# thermo_r1.net
KiCad netlist of a schematic drawn in EAGLE
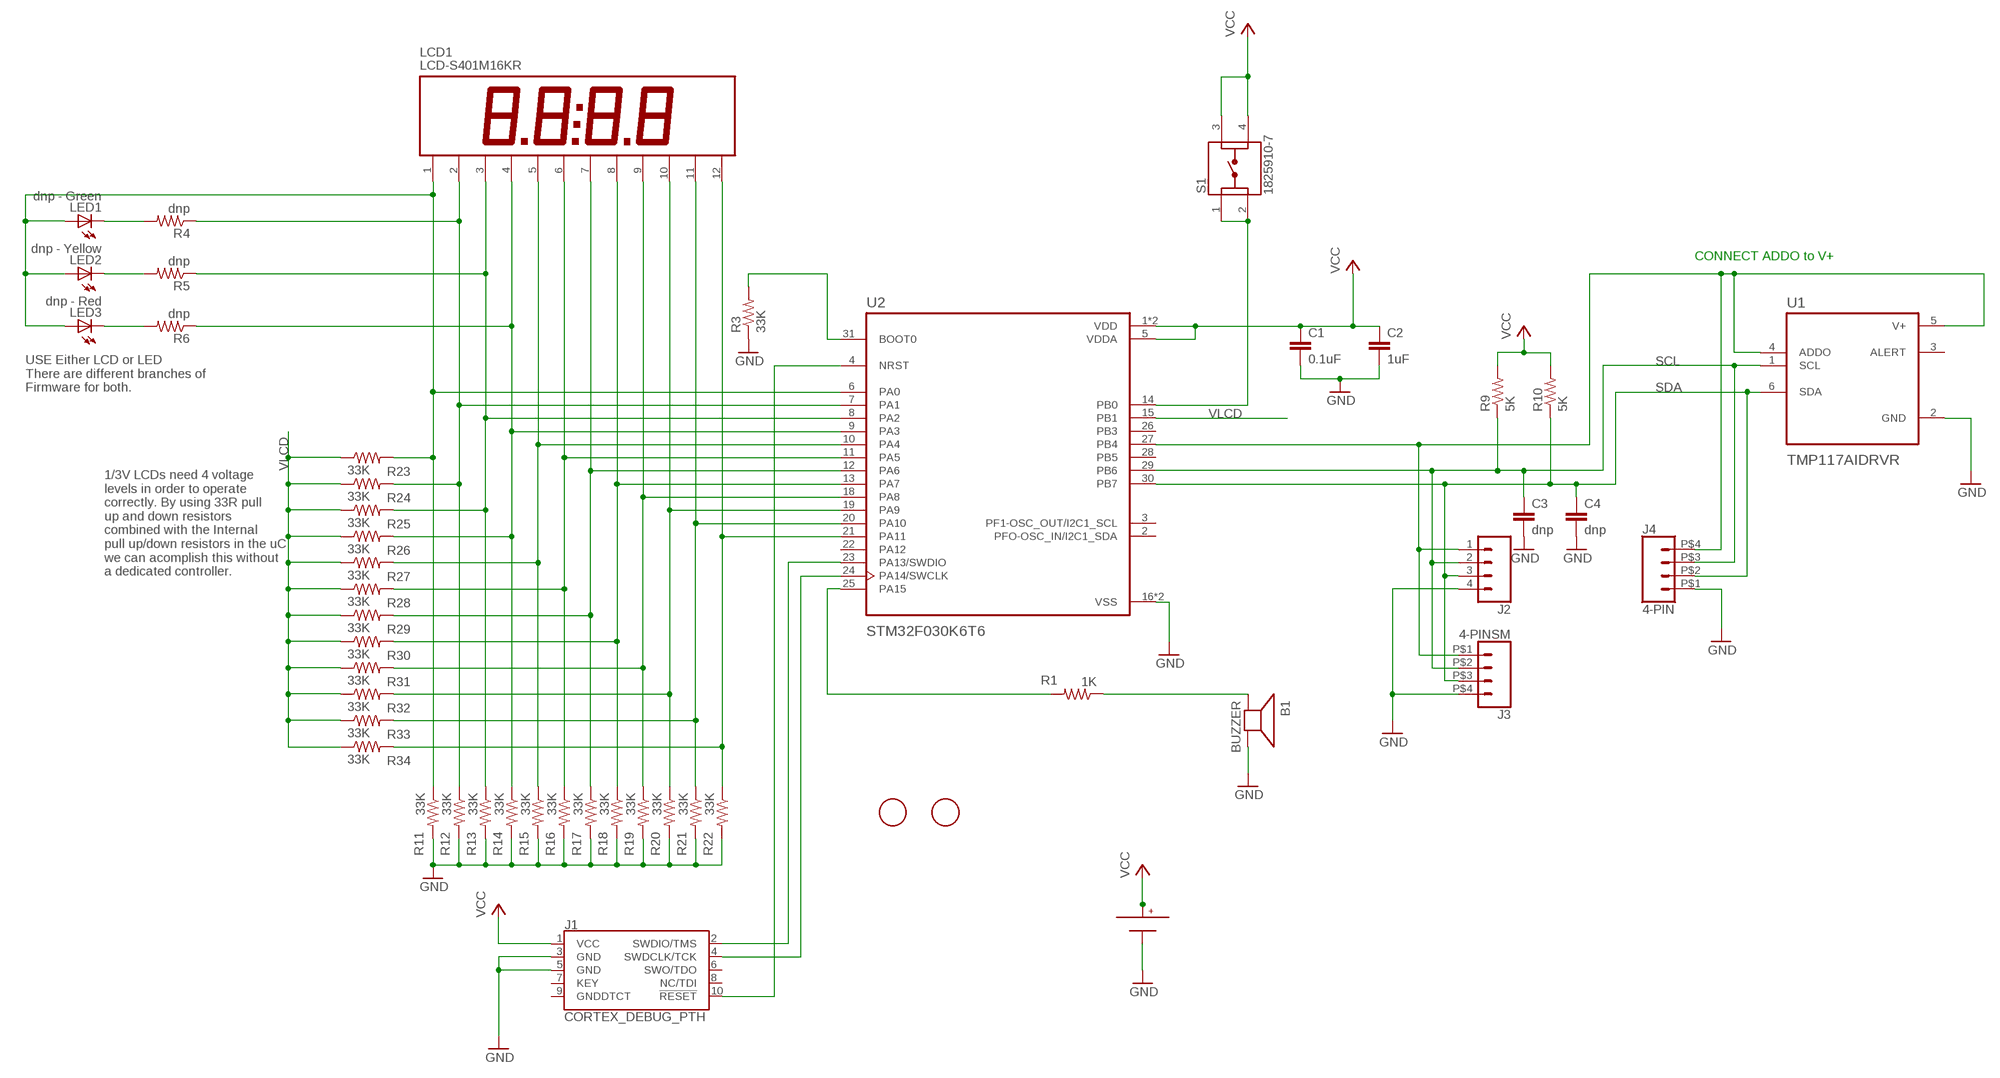
[diagram p0: schematic, sheet 1]

(export (version "E")
  (design (tool "Eeschema 10.0.6"))
  (components
    (comp (ref "B1")
      (value "BUZZER")
      (footprint "eagle-import:PLKCS1212E")
      (libsource (lib "eagle-import") (part "BUZZER"))
    )
    (comp (ref "BT1")
      (value "BAT-HLD-001")
      (footprint "eagle-import:BAT-HLD-001")
      (fields (field (name "MF") "Linx Technologies"))
      (libsource (lib "eagle-import") (part "BAT-HLD-001"))
    )
    (comp (ref "C1")
      (value "0.1uF")
      (footprint "eagle-import:R0603")
      (libsource (lib "eagle-import") (part "CAPACITORC0603"))
    )
    (comp (ref "C2")
      (value "1uF")
      (footprint "eagle-import:R0603")
      (libsource (lib "eagle-import") (part "CAPACITORC0603"))
    )
    (comp (ref "C3")
      (value "dnp")
      (footprint "eagle-import:R0603")
      (libsource (lib "eagle-import") (part "CAPACITORC0603"))
    )
    (comp (ref "C4")
      (value "dnp")
      (footprint "eagle-import:R0603")
      (libsource (lib "eagle-import") (part "CAPACITORC0603"))
    )
    (comp (ref "J1")
      (value "CORTEX_DEBUG_PTH")
      (footprint "eagle-import:2X5-PTH-1.27MM")
      (libsource (lib "eagle-import") (part "CORTEX_DEBUG_PTH"))
    )
    (comp (ref "J2")
      (value "CONN_041.27MM")
      (footprint "eagle-import:1X04_1.27MM")
      (libsource (lib "eagle-import") (part "CONN_041.27MM"))
    )
    (comp (ref "J3")
      (value "4-PINSM")
      (footprint "eagle-import:4PIN_1MM")
      (libsource (lib "eagle-import") (part "4-PINSM"))
    )
    (comp (ref "J4")
      (value "4-PIN")
      (footprint "eagle-import:2X2PIN_1MM")
      (libsource (lib "eagle-import") (part "4-PIN"))
    )
    (comp (ref "LCD1")
      (value "LCD-S401M16KR")
      (footprint "eagle-import:LCD-S401M16KR")
      (fields (field (name "MF") "Lumex Opto/Components"))
      (libsource (lib "eagle-import") (part "LCD-S401M16KR"))
    )
    (comp (ref "LED1")
      (value "dnp - Green")
      (footprint "eagle-import:CHIP-LED0805")
      (libsource (lib "eagle-import") (part "LEDCHIP-LED0805"))
    )
    (comp (ref "LED2")
      (value "dnp - Yellow")
      (footprint "eagle-import:CHIP-LED0805")
      (libsource (lib "eagle-import") (part "LEDCHIP-LED0805"))
    )
    (comp (ref "LED3")
      (value "dnp - Red")
      (footprint "eagle-import:CHIP-LED0805")
      (libsource (lib "eagle-import") (part "LEDCHIP-LED0805"))
    )
    (comp (ref "R1")
      (value "1K")
      (footprint "eagle-import:R0603")
      (libsource (lib "eagle-import") (part "RESISTORR0603"))
    )
    (comp (ref "R3")
      (value "33K")
      (footprint "eagle-import:R0603")
      (libsource (lib "eagle-import") (part "RESISTORR0603"))
    )
    (comp (ref "R4")
      (value "dnp")
      (footprint "eagle-import:R0603")
      (libsource (lib "eagle-import") (part "RESISTORR0603"))
    )
    (comp (ref "R5")
      (value "dnp")
      (footprint "eagle-import:R0603")
      (libsource (lib "eagle-import") (part "RESISTORR0603"))
    )
    (comp (ref "R6")
      (value "dnp")
      (footprint "eagle-import:R0603")
      (libsource (lib "eagle-import") (part "RESISTORR0603"))
    )
    (comp (ref "R9")
      (value "5K")
      (footprint "eagle-import:R0603")
      (libsource (lib "eagle-import") (part "RESISTORR0603"))
    )
    (comp (ref "R10")
      (value "5K")
      (footprint "eagle-import:R0603")
      (libsource (lib "eagle-import") (part "RESISTORR0603"))
    )
    (comp (ref "R11")
      (value "33K")
      (footprint "eagle-import:R0603")
      (libsource (lib "eagle-import") (part "RESISTORR0603"))
    )
    (comp (ref "R12")
      (value "33K")
      (footprint "eagle-import:R0603")
      (libsource (lib "eagle-import") (part "RESISTORR0603"))
    )
    (comp (ref "R13")
      (value "33K")
      (footprint "eagle-import:R0603")
      (libsource (lib "eagle-import") (part "RESISTORR0603"))
    )
    (comp (ref "R14")
      (value "33K")
      (footprint "eagle-import:R0603")
      (libsource (lib "eagle-import") (part "RESISTORR0603"))
    )
    (comp (ref "R15")
      (value "33K")
      (footprint "eagle-import:R0603")
      (libsource (lib "eagle-import") (part "RESISTORR0603"))
    )
    (comp (ref "R16")
      (value "33K")
      (footprint "eagle-import:R0603")
      (libsource (lib "eagle-import") (part "RESISTORR0603"))
    )
    (comp (ref "R17")
      (value "33K")
      (footprint "eagle-import:R0603")
      (libsource (lib "eagle-import") (part "RESISTORR0603"))
    )
    (comp (ref "R18")
      (value "33K")
      (footprint "eagle-import:R0603")
      (libsource (lib "eagle-import") (part "RESISTORR0603"))
    )
    (comp (ref "R19")
      (value "33K")
      (footprint "eagle-import:R0603")
      (libsource (lib "eagle-import") (part "RESISTORR0603"))
    )
    (comp (ref "R20")
      (value "33K")
      (footprint "eagle-import:R0603")
      (libsource (lib "eagle-import") (part "RESISTORR0603"))
    )
    (comp (ref "R21")
      (value "33K")
      (footprint "eagle-import:R0603")
      (libsource (lib "eagle-import") (part "RESISTORR0603"))
    )
    (comp (ref "R22")
      (value "33K")
      (footprint "eagle-import:R0603")
      (libsource (lib "eagle-import") (part "RESISTORR0603"))
    )
    (comp (ref "R23")
      (value "33K")
      (footprint "eagle-import:R0603")
      (libsource (lib "eagle-import") (part "RESISTORR0603"))
    )
    (comp (ref "R24")
      (value "33K")
      (footprint "eagle-import:R0603")
      (libsource (lib "eagle-import") (part "RESISTORR0603"))
    )
    (comp (ref "R25")
      (value "33K")
      (footprint "eagle-import:R0603")
      (libsource (lib "eagle-import") (part "RESISTORR0603"))
    )
    (comp (ref "R26")
      (value "33K")
      (footprint "eagle-import:R0603")
      (libsource (lib "eagle-import") (part "RESISTORR0603"))
    )
    (comp (ref "R27")
      (value "33K")
      (footprint "eagle-import:R0603")
      (libsource (lib "eagle-import") (part "RESISTORR0603"))
    )
    (comp (ref "R28")
      (value "33K")
      (footprint "eagle-import:R0603")
      (libsource (lib "eagle-import") (part "RESISTORR0603"))
    )
    (comp (ref "R29")
      (value "33K")
      (footprint "eagle-import:R0603")
      (libsource (lib "eagle-import") (part "RESISTORR0603"))
    )
    (comp (ref "R30")
      (value "33K")
      (footprint "eagle-import:R0603")
      (libsource (lib "eagle-import") (part "RESISTORR0603"))
    )
    (comp (ref "R31")
      (value "33K")
      (footprint "eagle-import:R0603")
      (libsource (lib "eagle-import") (part "RESISTORR0603"))
    )
    (comp (ref "R32")
      (value "33K")
      (footprint "eagle-import:R0603")
      (libsource (lib "eagle-import") (part "RESISTORR0603"))
    )
    (comp (ref "R33")
      (value "33K")
      (footprint "eagle-import:R0603")
      (libsource (lib "eagle-import") (part "RESISTORR0603"))
    )
    (comp (ref "R34")
      (value "33K")
      (footprint "eagle-import:R0603")
      (libsource (lib "eagle-import") (part "RESISTORR0603"))
    )
    (comp (ref "S1")
      (value "1825910-7")
      (footprint "eagle-import:SW_1825910-7")
      (fields (field (name "MF") "TE Connectivity"))
      (libsource (lib "eagle-import") (part "1825910-7"))
    )
    (comp (ref "U$5")
      (value "FIDUCIAL")
      (footprint "eagle-import:FIDUCIAL_1MM")
      (libsource (lib "eagle-import") (part "FIDUCIAL"))
    )
    (comp (ref "U$6")
      (value "FIDUCIAL")
      (footprint "eagle-import:FIDUCIAL_1MM")
      (libsource (lib "eagle-import") (part "FIDUCIAL"))
    )
    (comp (ref "U1")
      (value "TMP117AIDRVR")
      (footprint "eagle-import:SON65P200X200X80-7N")
      (fields (field (name "MF") "Texas Instruments"))
      (libsource (lib "eagle-import") (part "TMP117AIDRVR"))
    )
    (comp (ref "U2")
      (value "STM32F030K6T6")
      (footprint "eagle-import:QFP80P900X900X160-32N")
      (fields (field (name "MF") "STMicroelectronics"))
      (libsource (lib "eagle-import") (part "STM32F030K6T6"))
    )
  )
  (nets
    (net (code "1") (name "/SCL") (class "Default")
      (node (ref "C3") (pin "1") (pinfunction "1_1") (pintype "passive"))
      (node (ref "J2") (pin "2") (pinfunction "2_2") (pintype "passive"))
      (node (ref "J3") (pin "P$2") (pinfunction "2_P$2") (pintype "passive"))
      (node (ref "J4") (pin "P$3") (pinfunction "3_P$3") (pintype "passive"))
      (node (ref "R9") (pin "1") (pinfunction "1_1") (pintype "passive"))
      (node (ref "U1") (pin "1") (pinfunction "SCL_1") (pintype "input"))
      (node (ref "U2") (pin "29") (pinfunction "PB6_29") (pintype "bidirectional"))
    )
    (net (code "2") (name "/SDA") (class "Default")
      (node (ref "C4") (pin "1") (pinfunction "1_1") (pintype "passive"))
      (node (ref "J2") (pin "3") (pinfunction "3_3") (pintype "passive"))
      (node (ref "J3") (pin "P$3") (pinfunction "3_P$3") (pintype "passive"))
      (node (ref "J4") (pin "P$2") (pinfunction "2_P$2") (pintype "passive"))
      (node (ref "R10") (pin "1") (pinfunction "1_1") (pintype "passive"))
      (node (ref "U1") (pin "6") (pinfunction "SDA_6") (pintype "bidirectional"))
      (node (ref "U2") (pin "30") (pinfunction "PB7_30") (pintype "bidirectional"))
    )
    (net (code "3") (name "/VLCD") (class "Default")
      (node (ref "R23") (pin "1") (pinfunction "1_1") (pintype "passive"))
      (node (ref "R24") (pin "1") (pinfunction "1_1") (pintype "passive"))
      (node (ref "R25") (pin "1") (pinfunction "1_1") (pintype "passive"))
      (node (ref "R26") (pin "1") (pinfunction "1_1") (pintype "passive"))
      (node (ref "R27") (pin "1") (pinfunction "1_1") (pintype "passive"))
      (node (ref "R28") (pin "1") (pinfunction "1_1") (pintype "passive"))
      (node (ref "R29") (pin "1") (pinfunction "1_1") (pintype "passive"))
      (node (ref "R30") (pin "1") (pinfunction "1_1") (pintype "passive"))
      (node (ref "R31") (pin "1") (pinfunction "1_1") (pintype "passive"))
      (node (ref "R32") (pin "1") (pinfunction "1_1") (pintype "passive"))
      (node (ref "R33") (pin "1") (pinfunction "1_1") (pintype "passive"))
      (node (ref "R34") (pin "1") (pinfunction "1_1") (pintype "passive"))
      (node (ref "U2") (pin "15") (pinfunction "PB1_15") (pintype "bidirectional"))
    )
    (net (code "4") (name "GND") (class "Default")
      (node (ref "B1") (pin "P$2") (pinfunction "-_P$2") (pintype "passive"))
      (node (ref "BT1") (pin "-") (pinfunction "-_-") (pintype "bidirectional"))
      (node (ref "C1") (pin "2") (pinfunction "2_2") (pintype "passive"))
      (node (ref "C2") (pin "2") (pinfunction "2_2") (pintype "passive"))
      (node (ref "C3") (pin "2") (pinfunction "2_2") (pintype "passive"))
      (node (ref "C4") (pin "2") (pinfunction "2_2") (pintype "passive"))
      (node (ref "J1") (pin "3") (pinfunction "GND_3") (pintype "bidirectional"))
      (node (ref "J1") (pin "5") (pinfunction "GND_5") (pintype "bidirectional"))
      (node (ref "J2") (pin "4") (pinfunction "4_4") (pintype "passive"))
      (node (ref "J3") (pin "P$4") (pinfunction "4_P$4") (pintype "passive"))
      (node (ref "J4") (pin "P$1") (pinfunction "1_P$1") (pintype "passive"))
      (node (ref "R11") (pin "2") (pinfunction "2_2") (pintype "passive"))
      (node (ref "R12") (pin "2") (pinfunction "2_2") (pintype "passive"))
      (node (ref "R13") (pin "2") (pinfunction "2_2") (pintype "passive"))
      (node (ref "R14") (pin "2") (pinfunction "2_2") (pintype "passive"))
      (node (ref "R15") (pin "2") (pinfunction "2_2") (pintype "passive"))
      (node (ref "R16") (pin "2") (pinfunction "2_2") (pintype "passive"))
      (node (ref "R17") (pin "2") (pinfunction "2_2") (pintype "passive"))
      (node (ref "R18") (pin "2") (pinfunction "2_2") (pintype "passive"))
      (node (ref "R19") (pin "2") (pinfunction "2_2") (pintype "passive"))
      (node (ref "R20") (pin "2") (pinfunction "2_2") (pintype "passive"))
      (node (ref "R21") (pin "2") (pinfunction "2_2") (pintype "passive"))
      (node (ref "R22") (pin "2") (pinfunction "2_2") (pintype "passive"))
      (node (ref "R3") (pin "1") (pinfunction "1_1") (pintype "passive"))
      (node (ref "U1") (pin "2") (pinfunction "GND_2") (pintype "power_in"))
      (node (ref "U2") (pin "16") (pinfunction "VSS_16") (pintype "power_in"))
      (node (ref "U2") (pin "32") (pinfunction "VSS_32") (pintype "power_in"))
    )
    (net (code "5") (name "Net-(B1-+)") (class "Default")
      (node (ref "B1") (pin "P$1") (pinfunction "+_P$1") (pintype "passive"))
      (node (ref "R1") (pin "1") (pinfunction "1_1") (pintype "passive"))
    )
    (net (code "6") (name "Net-(J1-SWDCLK{slash}TCK)") (class "Default")
      (node (ref "J1") (pin "4") (pinfunction "SWDCLK/TCK_4") (pintype "bidirectional"))
      (node (ref "U2") (pin "24") (pinfunction "PA14/SWCLK_24") (pintype "bidirectional"))
    )
    (net (code "7") (name "Net-(J1-SWDIO{slash}TMS)") (class "Default")
      (node (ref "J1") (pin "2") (pinfunction "SWDIO/TMS_2") (pintype "bidirectional"))
      (node (ref "U2") (pin "23") (pinfunction "PA13/SWDIO_23") (pintype "bidirectional"))
    )
    (net (code "8") (name "Net-(J1-~{RESET})") (class "Default")
      (node (ref "J1") (pin "10") (pinfunction "~{RESET}_10") (pintype "bidirectional"))
      (node (ref "U2") (pin "4") (pinfunction "NRST_4") (pintype "bidirectional"))
    )
    (net (code "9") (name "Net-(J3-1)") (class "Default")
      (node (ref "J2") (pin "1") (pinfunction "1_1") (pintype "passive"))
      (node (ref "J3") (pin "P$1") (pinfunction "1_P$1") (pintype "passive"))
      (node (ref "J4") (pin "P$4") (pinfunction "4_P$4") (pintype "passive"))
      (node (ref "U1") (pin "4") (pinfunction "ADDO_4") (pintype "input"))
      (node (ref "U1") (pin "5") (pinfunction "V+_5") (pintype "power_in"))
      (node (ref "U2") (pin "27") (pinfunction "PB4_27") (pintype "bidirectional"))
    )
    (net (code "10") (name "Net-(LCD1-P$1)") (class "Default")
      (node (ref "LCD1") (pin "1") (pinfunction "P$1_1") (pintype "bidirectional"))
      (node (ref "LED1") (pin "A") (pinfunction "A_A") (pintype "passive"))
      (node (ref "LED2") (pin "A") (pinfunction "A_A") (pintype "passive"))
      (node (ref "LED3") (pin "A") (pinfunction "A_A") (pintype "passive"))
      (node (ref "R11") (pin "1") (pinfunction "1_1") (pintype "passive"))
      (node (ref "R23") (pin "2") (pinfunction "2_2") (pintype "passive"))
      (node (ref "U2") (pin "6") (pinfunction "PA0_6") (pintype "bidirectional"))
    )
    (net (code "11") (name "Net-(LCD1-P$2)") (class "Default")
      (node (ref "LCD1") (pin "2") (pinfunction "P$2_2") (pintype "bidirectional"))
      (node (ref "R12") (pin "1") (pinfunction "1_1") (pintype "passive"))
      (node (ref "R24") (pin "2") (pinfunction "2_2") (pintype "passive"))
      (node (ref "R4") (pin "1") (pinfunction "1_1") (pintype "passive"))
      (node (ref "U2") (pin "7") (pinfunction "PA1_7") (pintype "bidirectional"))
    )
    (net (code "12") (name "Net-(LCD1-P$3)") (class "Default")
      (node (ref "LCD1") (pin "3") (pinfunction "P$3_3") (pintype "bidirectional"))
      (node (ref "R13") (pin "1") (pinfunction "1_1") (pintype "passive"))
      (node (ref "R25") (pin "2") (pinfunction "2_2") (pintype "passive"))
      (node (ref "R5") (pin "1") (pinfunction "1_1") (pintype "passive"))
      (node (ref "U2") (pin "8") (pinfunction "PA2_8") (pintype "bidirectional"))
    )
    (net (code "13") (name "Net-(LCD1-P$4)") (class "Default")
      (node (ref "LCD1") (pin "4") (pinfunction "P$4_4") (pintype "bidirectional"))
      (node (ref "R14") (pin "1") (pinfunction "1_1") (pintype "passive"))
      (node (ref "R26") (pin "2") (pinfunction "2_2") (pintype "passive"))
      (node (ref "R6") (pin "1") (pinfunction "1_1") (pintype "passive"))
      (node (ref "U2") (pin "9") (pinfunction "PA3_9") (pintype "bidirectional"))
    )
    (net (code "14") (name "Net-(LCD1-P$5)") (class "Default")
      (node (ref "LCD1") (pin "5") (pinfunction "P$5_5") (pintype "bidirectional"))
      (node (ref "R15") (pin "1") (pinfunction "1_1") (pintype "passive"))
      (node (ref "R27") (pin "2") (pinfunction "2_2") (pintype "passive"))
      (node (ref "U2") (pin "10") (pinfunction "PA4_10") (pintype "bidirectional"))
    )
    (net (code "15") (name "Net-(LCD1-P$6)") (class "Default")
      (node (ref "LCD1") (pin "6") (pinfunction "P$6_6") (pintype "bidirectional"))
      (node (ref "R16") (pin "1") (pinfunction "1_1") (pintype "passive"))
      (node (ref "R28") (pin "2") (pinfunction "2_2") (pintype "passive"))
      (node (ref "U2") (pin "11") (pinfunction "PA5_11") (pintype "bidirectional"))
    )
    (net (code "16") (name "Net-(LCD1-P$7)") (class "Default")
      (node (ref "LCD1") (pin "7") (pinfunction "P$7_7") (pintype "bidirectional"))
      (node (ref "R17") (pin "1") (pinfunction "1_1") (pintype "passive"))
      (node (ref "R29") (pin "2") (pinfunction "2_2") (pintype "passive"))
      (node (ref "U2") (pin "12") (pinfunction "PA6_12") (pintype "bidirectional"))
    )
    (net (code "17") (name "Net-(LCD1-P$8)") (class "Default")
      (node (ref "LCD1") (pin "8") (pinfunction "P$8_8") (pintype "bidirectional"))
      (node (ref "R18") (pin "1") (pinfunction "1_1") (pintype "passive"))
      (node (ref "R30") (pin "2") (pinfunction "2_2") (pintype "passive"))
      (node (ref "U2") (pin "13") (pinfunction "PA7_13") (pintype "bidirectional"))
    )
    (net (code "18") (name "Net-(LCD1-P$9)") (class "Default")
      (node (ref "LCD1") (pin "9") (pinfunction "P$9_9") (pintype "bidirectional"))
      (node (ref "R19") (pin "1") (pinfunction "1_1") (pintype "passive"))
      (node (ref "R31") (pin "2") (pinfunction "2_2") (pintype "passive"))
      (node (ref "U2") (pin "18") (pinfunction "PA8_18") (pintype "bidirectional"))
    )
    (net (code "19") (name "Net-(LCD1-P$10)") (class "Default")
      (node (ref "LCD1") (pin "10") (pinfunction "P$10_10") (pintype "bidirectional"))
      (node (ref "R20") (pin "1") (pinfunction "1_1") (pintype "passive"))
      (node (ref "R32") (pin "2") (pinfunction "2_2") (pintype "passive"))
      (node (ref "U2") (pin "19") (pinfunction "PA9_19") (pintype "bidirectional"))
    )
    (net (code "20") (name "Net-(LCD1-P$11)") (class "Default")
      (node (ref "LCD1") (pin "11") (pinfunction "P$11_11") (pintype "bidirectional"))
      (node (ref "R21") (pin "1") (pinfunction "1_1") (pintype "passive"))
      (node (ref "R33") (pin "2") (pinfunction "2_2") (pintype "passive"))
      (node (ref "U2") (pin "20") (pinfunction "PA10_20") (pintype "bidirectional"))
    )
    (net (code "21") (name "Net-(LCD1-P$12)") (class "Default")
      (node (ref "LCD1") (pin "12") (pinfunction "P$12_12") (pintype "bidirectional"))
      (node (ref "R22") (pin "1") (pinfunction "1_1") (pintype "passive"))
      (node (ref "R34") (pin "2") (pinfunction "2_2") (pintype "passive"))
      (node (ref "U2") (pin "21") (pinfunction "PA11_21") (pintype "bidirectional"))
    )
    (net (code "22") (name "Net-(LED1-PadC)") (class "Default")
      (node (ref "LED1") (pin "C") (pinfunction "C_C") (pintype "passive"))
      (node (ref "R4") (pin "2") (pinfunction "2_2") (pintype "passive"))
    )
    (net (code "23") (name "Net-(LED2-PadC)") (class "Default")
      (node (ref "LED2") (pin "C") (pinfunction "C_C") (pintype "passive"))
      (node (ref "R5") (pin "2") (pinfunction "2_2") (pintype "passive"))
    )
    (net (code "24") (name "Net-(LED3-PadC)") (class "Default")
      (node (ref "LED3") (pin "C") (pinfunction "C_C") (pintype "passive"))
      (node (ref "R6") (pin "2") (pinfunction "2_2") (pintype "passive"))
    )
    (net (code "25") (name "Net-(U2-BOOT0)") (class "Default")
      (node (ref "R3") (pin "2") (pinfunction "2_2") (pintype "passive"))
      (node (ref "U2") (pin "31") (pinfunction "BOOT0_31") (pintype "input"))
    )
    (net (code "26") (name "Net-(U2-PA15)") (class "Default")
      (node (ref "R1") (pin "2") (pinfunction "2_2") (pintype "passive"))
      (node (ref "U2") (pin "25") (pinfunction "PA15_25") (pintype "bidirectional"))
    )
    (net (code "27") (name "Net-(U2-PB0)") (class "Default")
      (node (ref "S1") (pin "1") (pinfunction "1_1") (pintype "passive"))
      (node (ref "S1") (pin "2") (pinfunction "2_2") (pintype "passive"))
      (node (ref "U2") (pin "14") (pinfunction "PB0_14") (pintype "bidirectional"))
    )
    (net (code "28") (name "VCC") (class "Default")
      (node (ref "BT1") (pin "+@1") (pinfunction "+_+@1") (pintype "bidirectional"))
      (node (ref "BT1") (pin "+@2") (pinfunction "+_+@2") (pintype "bidirectional"))
      (node (ref "C1") (pin "1") (pinfunction "1_1") (pintype "passive"))
      (node (ref "C2") (pin "1") (pinfunction "1_1") (pintype "passive"))
      (node (ref "J1") (pin "1") (pinfunction "VCC_1") (pintype "bidirectional"))
      (node (ref "R10") (pin "2") (pinfunction "2_2") (pintype "passive"))
      (node (ref "R9") (pin "2") (pinfunction "2_2") (pintype "passive"))
      (node (ref "S1") (pin "3") (pinfunction "3_3") (pintype "passive"))
      (node (ref "S1") (pin "4") (pinfunction "4_4") (pintype "passive"))
      (node (ref "U2") (pin "1") (pinfunction "VDD_1") (pintype "power_in"))
      (node (ref "U2") (pin "17") (pinfunction "VDD_17") (pintype "power_in"))
      (node (ref "U2") (pin "5") (pinfunction "VDDA_5") (pintype "power_in"))
    )
    (net (code "29") (name "unconnected-(J1-GNDDTCT-Pad9)") (class "Default")
      (node (ref "J1") (pin "9") (pinfunction "GNDDTCT_9") (pintype "bidirectional"))
    )
    (net (code "30") (name "unconnected-(J1-KEY-Pad7)") (class "Default")
      (node (ref "J1") (pin "7") (pinfunction "KEY_7") (pintype "bidirectional"))
    )
    (net (code "31") (name "unconnected-(J1-NC{slash}TDI-Pad8)") (class "Default")
      (node (ref "J1") (pin "8") (pinfunction "NC/TDI_8") (pintype "bidirectional"))
    )
    (net (code "32") (name "unconnected-(J1-SWO{slash}TDO-Pad6)") (class "Default")
      (node (ref "J1") (pin "6") (pinfunction "SWO/TDO_6") (pintype "bidirectional"))
    )
    (net (code "33") (name "unconnected-(U1-ALERT-Pad3)") (class "Default")
      (node (ref "U1") (pin "3") (pinfunction "ALERT_3") (pintype "output"))
    )
    (net (code "34") (name "unconnected-(U2-PA12-Pad22)") (class "Default")
      (node (ref "U2") (pin "22") (pinfunction "PA12_22") (pintype "bidirectional"))
    )
    (net (code "35") (name "unconnected-(U2-PB3-Pad26)") (class "Default")
      (node (ref "U2") (pin "26") (pinfunction "PB3_26") (pintype "bidirectional"))
    )
    (net (code "36") (name "unconnected-(U2-PB5-Pad28)") (class "Default")
      (node (ref "U2") (pin "28") (pinfunction "PB5_28") (pintype "bidirectional"))
    )
    (net (code "37") (name "unconnected-(U2-PF1-OSC_OUT{slash}I2C1_SCL-Pad3)") (class "Default")
      (node (ref "U2") (pin "3") (pinfunction "PF1-OSC_OUT/I2C1_SCL_3") (pintype "bidirectional"))
    )
    (net (code "38") (name "unconnected-(U2-PFO-OSC_IN{slash}I2C1_SDA-Pad2)") (class "Default")
      (node (ref "U2") (pin "2") (pinfunction "PFO-OSC_IN/I2C1_SDA_2") (pintype "bidirectional"))
    )
  )
)
